# MCU.net
KiCad netlist of a schematic drawn in Altium Designer
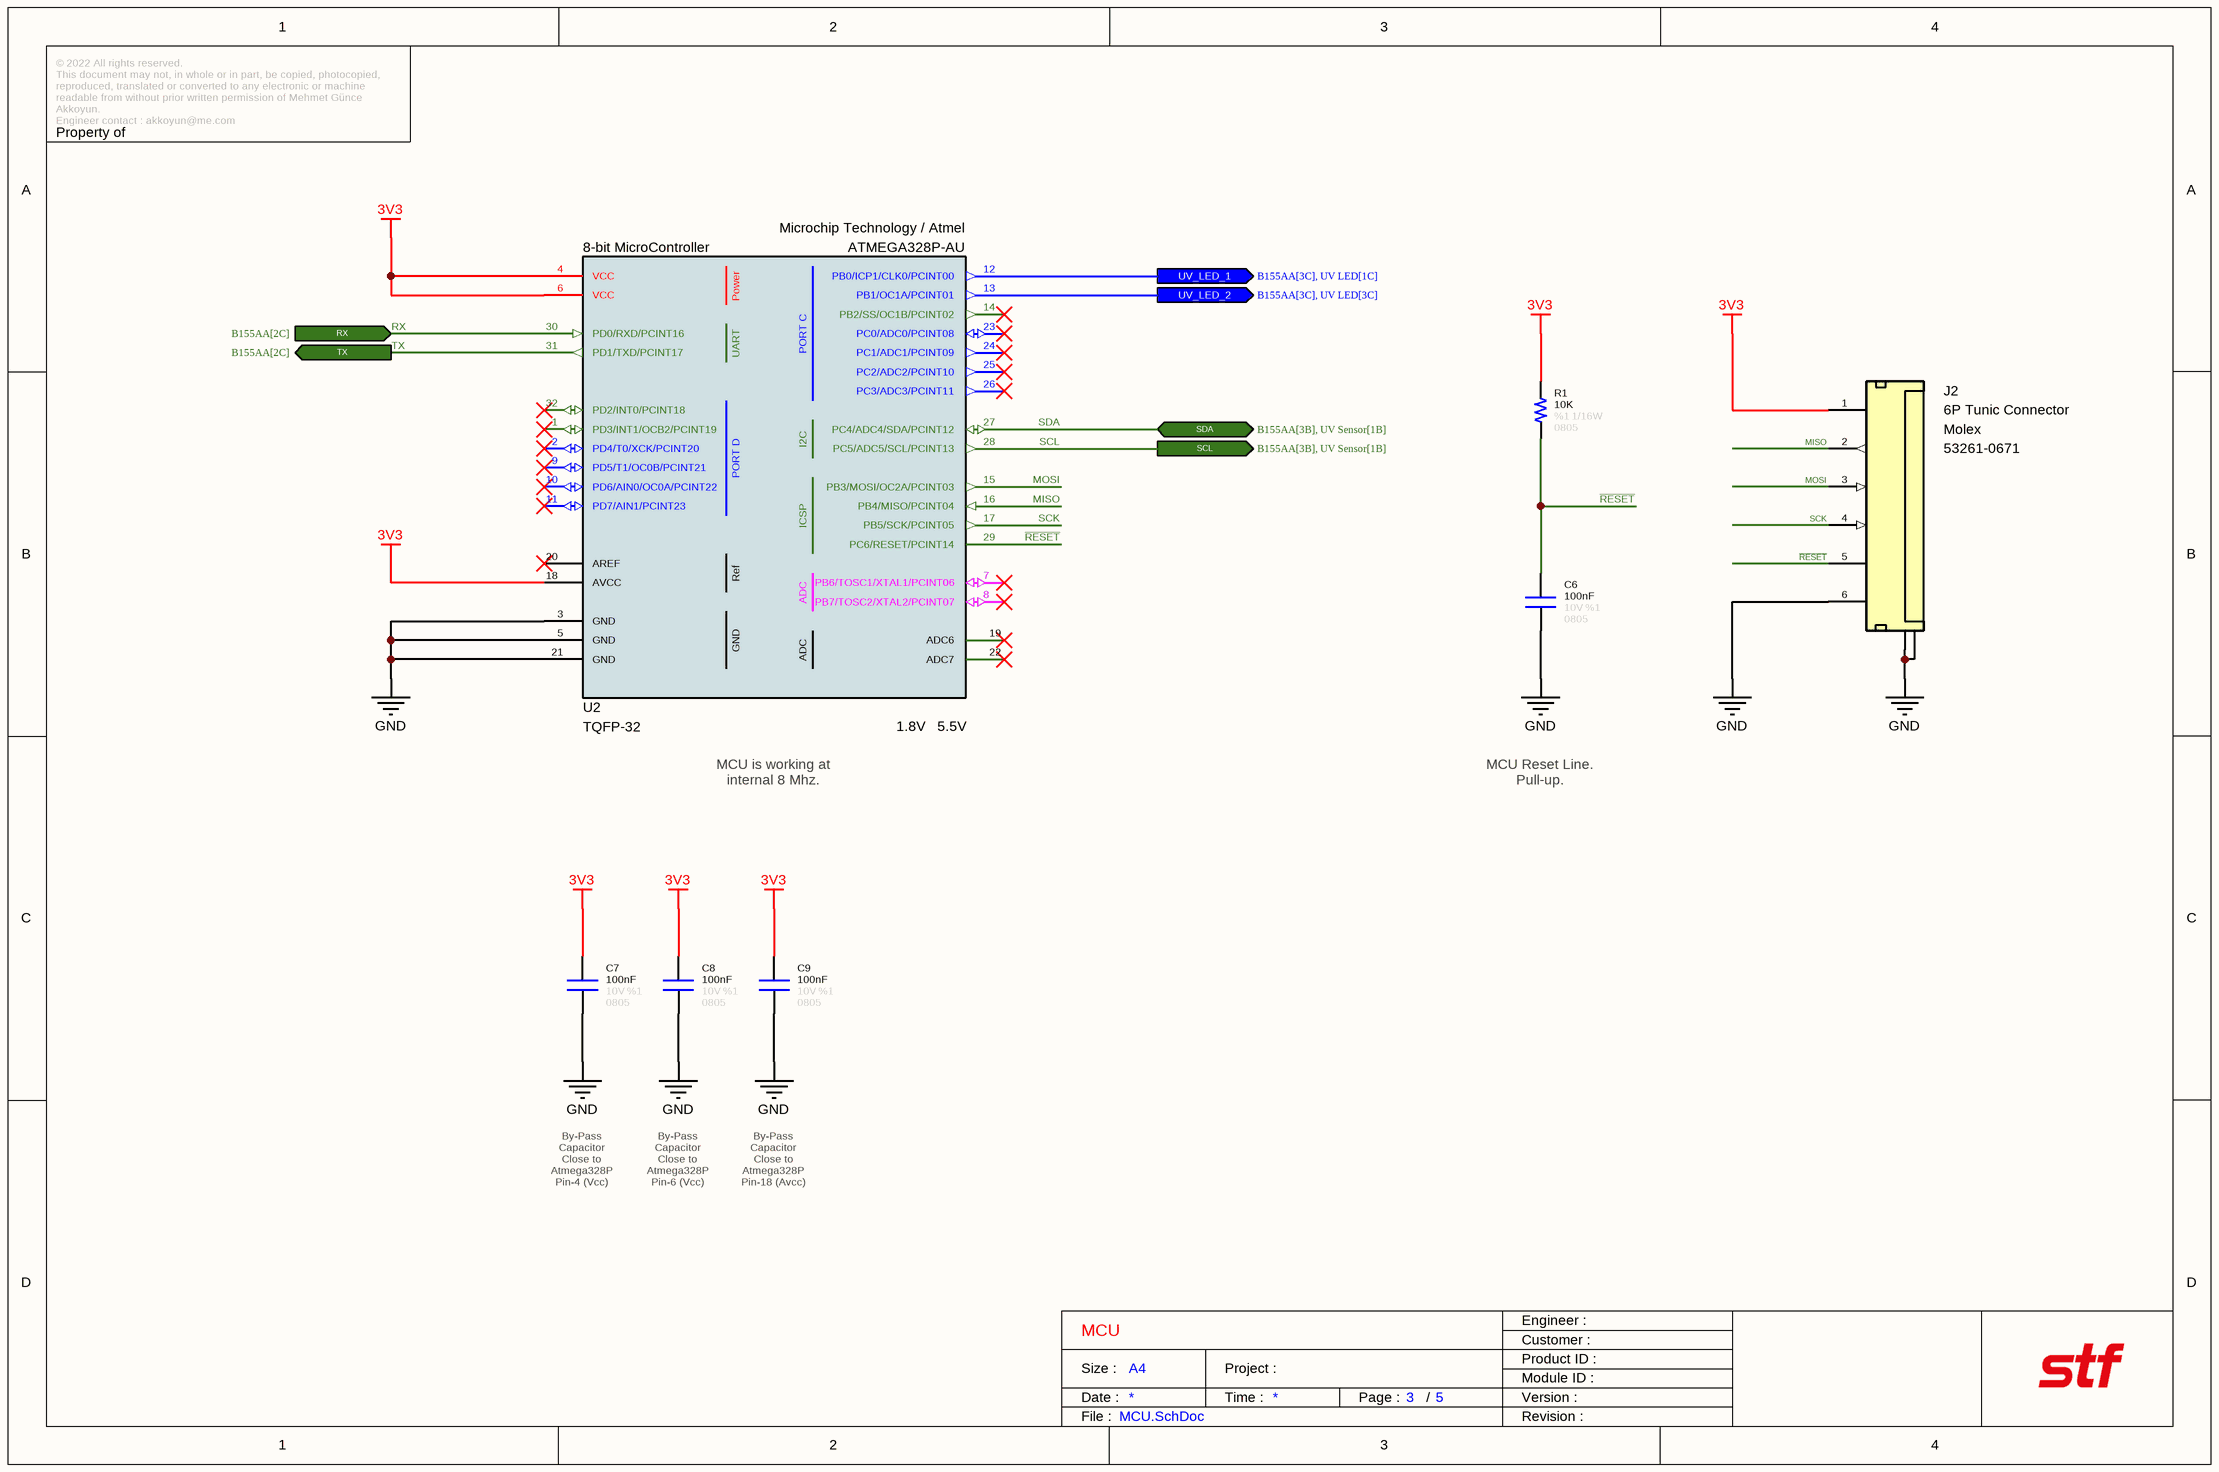
[diagram p0: MCU.SchDoc]

(export (version "E")
  (design (tool "Eeschema 10.0.6"))
  (components
    (comp (ref "C6")
      (value "100nF")
      (footprint "CAPACITOR_0805")
      (description "Capacitor (MLCC) - 100nF / 10V / 0805")
      (fields
        (field (name "MANUFACTURER PART NUMBER") "C0805C104K8JACAUTO")
        (field (name "TOLERANCE") "%1")
        (field (name "VOLTAGE") "10V")
        (field (name "CASE") "0805")
        (field (name "Comment") "Capacitor - 100nF [0805] (MLCC)")
      )
      (libsource (lib "Akkoyun") (part "Capacitor - 100nF [0805-10V]"))
    )
    (comp (ref "C7")
      (value "100nF")
      (footprint "CAPACITOR_0805")
      (description "Capacitor (MLCC) - 100nF / 10V / 0805")
      (fields
        (field (name "MANUFACTURER PART NUMBER") "C0805C104K8JACAUTO")
        (field (name "TOLERANCE") "%1")
        (field (name "VOLTAGE") "10V")
        (field (name "CASE") "0805")
        (field (name "Comment") "Capacitor - 100nF [0805] (MLCC)")
      )
      (libsource (lib "Akkoyun") (part "Capacitor - 100nF [0805-10V]"))
    )
    (comp (ref "C8")
      (value "100nF")
      (footprint "CAPACITOR_0805")
      (description "Capacitor (MLCC) - 100nF / 10V / 0805")
      (fields
        (field (name "MANUFACTURER PART NUMBER") "C0805C104K8JACAUTO")
        (field (name "TOLERANCE") "%1")
        (field (name "VOLTAGE") "10V")
        (field (name "CASE") "0805")
        (field (name "Comment") "Capacitor - 100nF [0805] (MLCC)")
      )
      (libsource (lib "Akkoyun") (part "Capacitor - 100nF [0805-10V]"))
    )
    (comp (ref "C9")
      (value "100nF")
      (footprint "CAPACITOR_0805")
      (description "Capacitor (MLCC) - 100nF / 10V / 0805")
      (fields
        (field (name "MANUFACTURER PART NUMBER") "C0805C104K8JACAUTO")
        (field (name "TOLERANCE") "%1")
        (field (name "VOLTAGE") "10V")
        (field (name "CASE") "0805")
        (field (name "Comment") "Capacitor - 100nF [0805] (MLCC)")
      )
      (libsource (lib "Akkoyun") (part "Capacitor - 100nF [0805-10V]"))
    )
    (comp (ref "J2")
      (value "6P Tunic Connector")
      (footprint "Connector_Tunic 6P")
      (description "Mini Tunic Connector with 6P")
      (fields
        (field (name "MANUFACTURER PART NUMBER") "53261-0671")
        (field (name "MANUFACTURER NAME") "Molex")
      )
      (libsource (lib "Akkoyun") (part "Connector - Mini Tunic 6P (1.25)"))
    )
    (comp (ref "R1")
      (value "10K")
      (footprint "RESISTOR_0805")
      (description "Thick Film Resistors - SMD 1/16 W 10 KOhm 1%")
      (fields
        (field (name "MANUFACTURER PART NUMBER") "CRCW040210K0FKED")
        (field (name "TOLERANCE") "%1")
        (field (name "CASE") "0805")
        (field (name "POWER") "1/16W")
        (field (name "Comment") "10K - 0805 - %1 - 1/16W")
      )
      (libsource (lib "Akkoyun") (part "Resistor - 10K [0805]"))
    )
    (comp (ref "U2")
      (value "8-bit MicroController")
      (footprint "TQFN-32")
      (description "8-bit Microcontrollers - MCU 32KB In-system Flash 20MHz 1.8V-5.5V")
      (fields
        (field (name "SUPPLY VOLTAGE - MAX") "5.5V")
        (field (name "SUPPLY VOLTAGE - MIN") "1.8V")
        (field (name "MANUFACTURER NAME") "Microchip Technology / Atmel")
        (field (name "MANUFACTURER PART NUMBER") "ATMEGA328P-AU")
        (field (name "CASE") "TQFP-32")
      )
      (libsource (lib "Akkoyun") (part "IC - ATMEGA328P-AU"))
    )
  )
  (nets
    (net (code "1") (name "/MISO") (class "Default")
      (node (ref "J2") (pin "2") (pinfunction "M_DRV_2") (pintype "output"))
      (node (ref "U2") (pin "16") (pinfunction "PB4/MISO/PCINT04_16") (pintype "input"))
    )
    (net (code "2") (name "/MOSI") (class "Default")
      (node (ref "J2") (pin "3") (pinfunction "M_DRV_3") (pintype "input"))
      (node (ref "U2") (pin "15") (pinfunction "PB3/MOSI/OC2A/PCINT03_15") (pintype "output"))
    )
    (net (code "3") (name "/RX") (class "Default")
      (node (ref "U2") (pin "30") (pinfunction "PD0/RXD/PCINT16_30") (pintype "input"))
    )
    (net (code "4") (name "/SCK") (class "Default")
      (node (ref "J2") (pin "4") (pinfunction "M_DRV_4") (pintype "input"))
      (node (ref "U2") (pin "17") (pinfunction "PB5/SCK/PCINT05_17") (pintype "output"))
    )
    (net (code "5") (name "/SCL") (class "Default")
      (node (ref "U2") (pin "28") (pinfunction "PC5/ADC5/SCL/PCINT13_28") (pintype "output"))
    )
    (net (code "6") (name "/SDA") (class "Default")
      (node (ref "U2") (pin "27") (pinfunction "PC4/ADC4/SDA/PCINT12_27") (pintype "bidirectional"))
    )
    (net (code "7") (name "/TX") (class "Default")
      (node (ref "U2") (pin "31") (pinfunction "PD1/TXD/PCINT17_31") (pintype "output"))
    )
    (net (code "8") (name "/UV_LED_1") (class "Default")
      (node (ref "U2") (pin "12") (pinfunction "PB0/ICP1/CLK0/PCINT00_12") (pintype "output"))
    )
    (net (code "9") (name "/UV_LED_2") (class "Default")
      (node (ref "U2") (pin "13") (pinfunction "PB1/OC1A/PCINT01_13") (pintype "output"))
    )
    (net (code "10") (name "/~{RESET}") (class "Default")
      (node (ref "C6") (pin "2") (pinfunction "2_2") (pintype "passive"))
      (node (ref "J2") (pin "5") (pinfunction "M_DRV_5") (pintype "passive"))
      (node (ref "R1") (pin "1") (pinfunction "1_1") (pintype "passive"))
      (node (ref "U2") (pin "29") (pinfunction "PC6/RESET/PCINT14_29") (pintype "passive"))
    )
    (net (code "11") (name "3V3") (class "Default")
      (node (ref "C7") (pin "2") (pinfunction "2_2") (pintype "passive"))
      (node (ref "C8") (pin "2") (pinfunction "2_2") (pintype "passive"))
      (node (ref "C9") (pin "2") (pinfunction "2_2") (pintype "passive"))
      (node (ref "J2") (pin "1") (pinfunction "VBAT_1") (pintype "passive"))
      (node (ref "R1") (pin "2") (pinfunction "2_2") (pintype "passive"))
      (node (ref "U2") (pin "18") (pinfunction "AVCC_18") (pintype "passive"))
      (node (ref "U2") (pin "4") (pinfunction "VCC_4") (pintype "power_in"))
      (node (ref "U2") (pin "6") (pinfunction "VCC_6") (pintype "power_in"))
    )
    (net (code "12") (name "GND") (class "Default")
      (node (ref "C6") (pin "1") (pinfunction "1_1") (pintype "passive"))
      (node (ref "C7") (pin "1") (pinfunction "1_1") (pintype "passive"))
      (node (ref "C8") (pin "1") (pinfunction "1_1") (pintype "passive"))
      (node (ref "C9") (pin "1") (pinfunction "1_1") (pintype "passive"))
      (node (ref "J2") (pin "6") (pinfunction "M_DRV_6") (pintype "passive"))
      (node (ref "J2") (pin "7") (pinfunction "GND_7") (pintype "passive"))
      (node (ref "J2") (pin "8") (pinfunction "GND_8") (pintype "passive"))
      (node (ref "U2") (pin "21") (pinfunction "GND_21") (pintype "power_in"))
      (node (ref "U2") (pin "3") (pinfunction "GND_3") (pintype "power_in"))
      (node (ref "U2") (pin "5") (pinfunction "GND_5") (pintype "power_in"))
    )
    (net (code "13") (name "unconnected-(U2-ADC6-Pad19)") (class "Default")
      (node (ref "U2") (pin "19") (pinfunction "ADC6_19") (pintype "passive+no_connect"))
    )
    (net (code "14") (name "unconnected-(U2-ADC7-Pad22)") (class "Default")
      (node (ref "U2") (pin "22") (pinfunction "ADC7_22") (pintype "passive+no_connect"))
    )
    (net (code "15") (name "unconnected-(U2-AREF-Pad20)") (class "Default")
      (node (ref "U2") (pin "20") (pinfunction "AREF_20") (pintype "passive+no_connect"))
    )
    (net (code "16") (name "unconnected-(U2-PB2{slash}SS{slash}OC1B{slash}PCINT02-Pad14)") (class "Default")
      (node (ref "U2") (pin "14") (pinfunction "PB2/SS/OC1B/PCINT02_14") (pintype "output+no_connect"))
    )
    (net (code "17") (name "unconnected-(U2-PB6{slash}TOSC1{slash}XTAL1{slash}PCINT06-Pad7)") (class "Default")
      (node (ref "U2") (pin "7") (pinfunction "PB6/TOSC1/XTAL1/PCINT06_7") (pintype "bidirectional+no_connect"))
    )
    (net (code "18") (name "unconnected-(U2-PB7{slash}TOSC2{slash}XTAL2{slash}PCINT07-Pad8)") (class "Default")
      (node (ref "U2") (pin "8") (pinfunction "PB7/TOSC2/XTAL2/PCINT07_8") (pintype "bidirectional+no_connect"))
    )
    (net (code "19") (name "unconnected-(U2-PC0{slash}ADC0{slash}PCINT08-Pad23)") (class "Default")
      (node (ref "U2") (pin "23") (pinfunction "PC0/ADC0/PCINT08_23") (pintype "bidirectional+no_connect"))
    )
    (net (code "20") (name "unconnected-(U2-PC1{slash}ADC1{slash}PCINT09-Pad24)") (class "Default")
      (node (ref "U2") (pin "24") (pinfunction "PC1/ADC1/PCINT09_24") (pintype "output+no_connect"))
    )
    (net (code "21") (name "unconnected-(U2-PC2{slash}ADC2{slash}PCINT10-Pad25)") (class "Default")
      (node (ref "U2") (pin "25") (pinfunction "PC2/ADC2/PCINT10_25") (pintype "output+no_connect"))
    )
    (net (code "22") (name "unconnected-(U2-PC3{slash}ADC3{slash}PCINT11-Pad26)") (class "Default")
      (node (ref "U2") (pin "26") (pinfunction "PC3/ADC3/PCINT11_26") (pintype "output+no_connect"))
    )
    (net (code "23") (name "unconnected-(U2-PD2{slash}INT0{slash}PCINT18-Pad32)") (class "Default")
      (node (ref "U2") (pin "32") (pinfunction "PD2/INT0/PCINT18_32") (pintype "bidirectional+no_connect"))
    )
    (net (code "24") (name "unconnected-(U2-PD3{slash}INT1{slash}OCB2{slash}PCINT19-Pad1)") (class "Default")
      (node (ref "U2") (pin "1") (pinfunction "PD3/INT1/OCB2/PCINT19_1") (pintype "bidirectional+no_connect"))
    )
    (net (code "25") (name "unconnected-(U2-PD4{slash}T0{slash}XCK{slash}PCINT20-Pad2)") (class "Default")
      (node (ref "U2") (pin "2") (pinfunction "PD4/T0/XCK/PCINT20_2") (pintype "bidirectional+no_connect"))
    )
    (net (code "26") (name "unconnected-(U2-PD5{slash}T1{slash}OC0B{slash}PCINT21-Pad9)") (class "Default")
      (node (ref "U2") (pin "9") (pinfunction "PD5/T1/OC0B/PCINT21_9") (pintype "bidirectional+no_connect"))
    )
    (net (code "27") (name "unconnected-(U2-PD6{slash}AIN0{slash}OC0A{slash}PCINT22-Pad10)") (class "Default")
      (node (ref "U2") (pin "10") (pinfunction "PD6/AIN0/OC0A/PCINT22_10") (pintype "bidirectional+no_connect"))
    )
    (net (code "28") (name "unconnected-(U2-PD7{slash}AIN1{slash}PCINT23-Pad11)") (class "Default")
      (node (ref "U2") (pin "11") (pinfunction "PD7/AIN1/PCINT23_11") (pintype "bidirectional+no_connect"))
    )
  )
)
